# fpv.net
KiCad netlist of a schematic drawn in Altium Designer
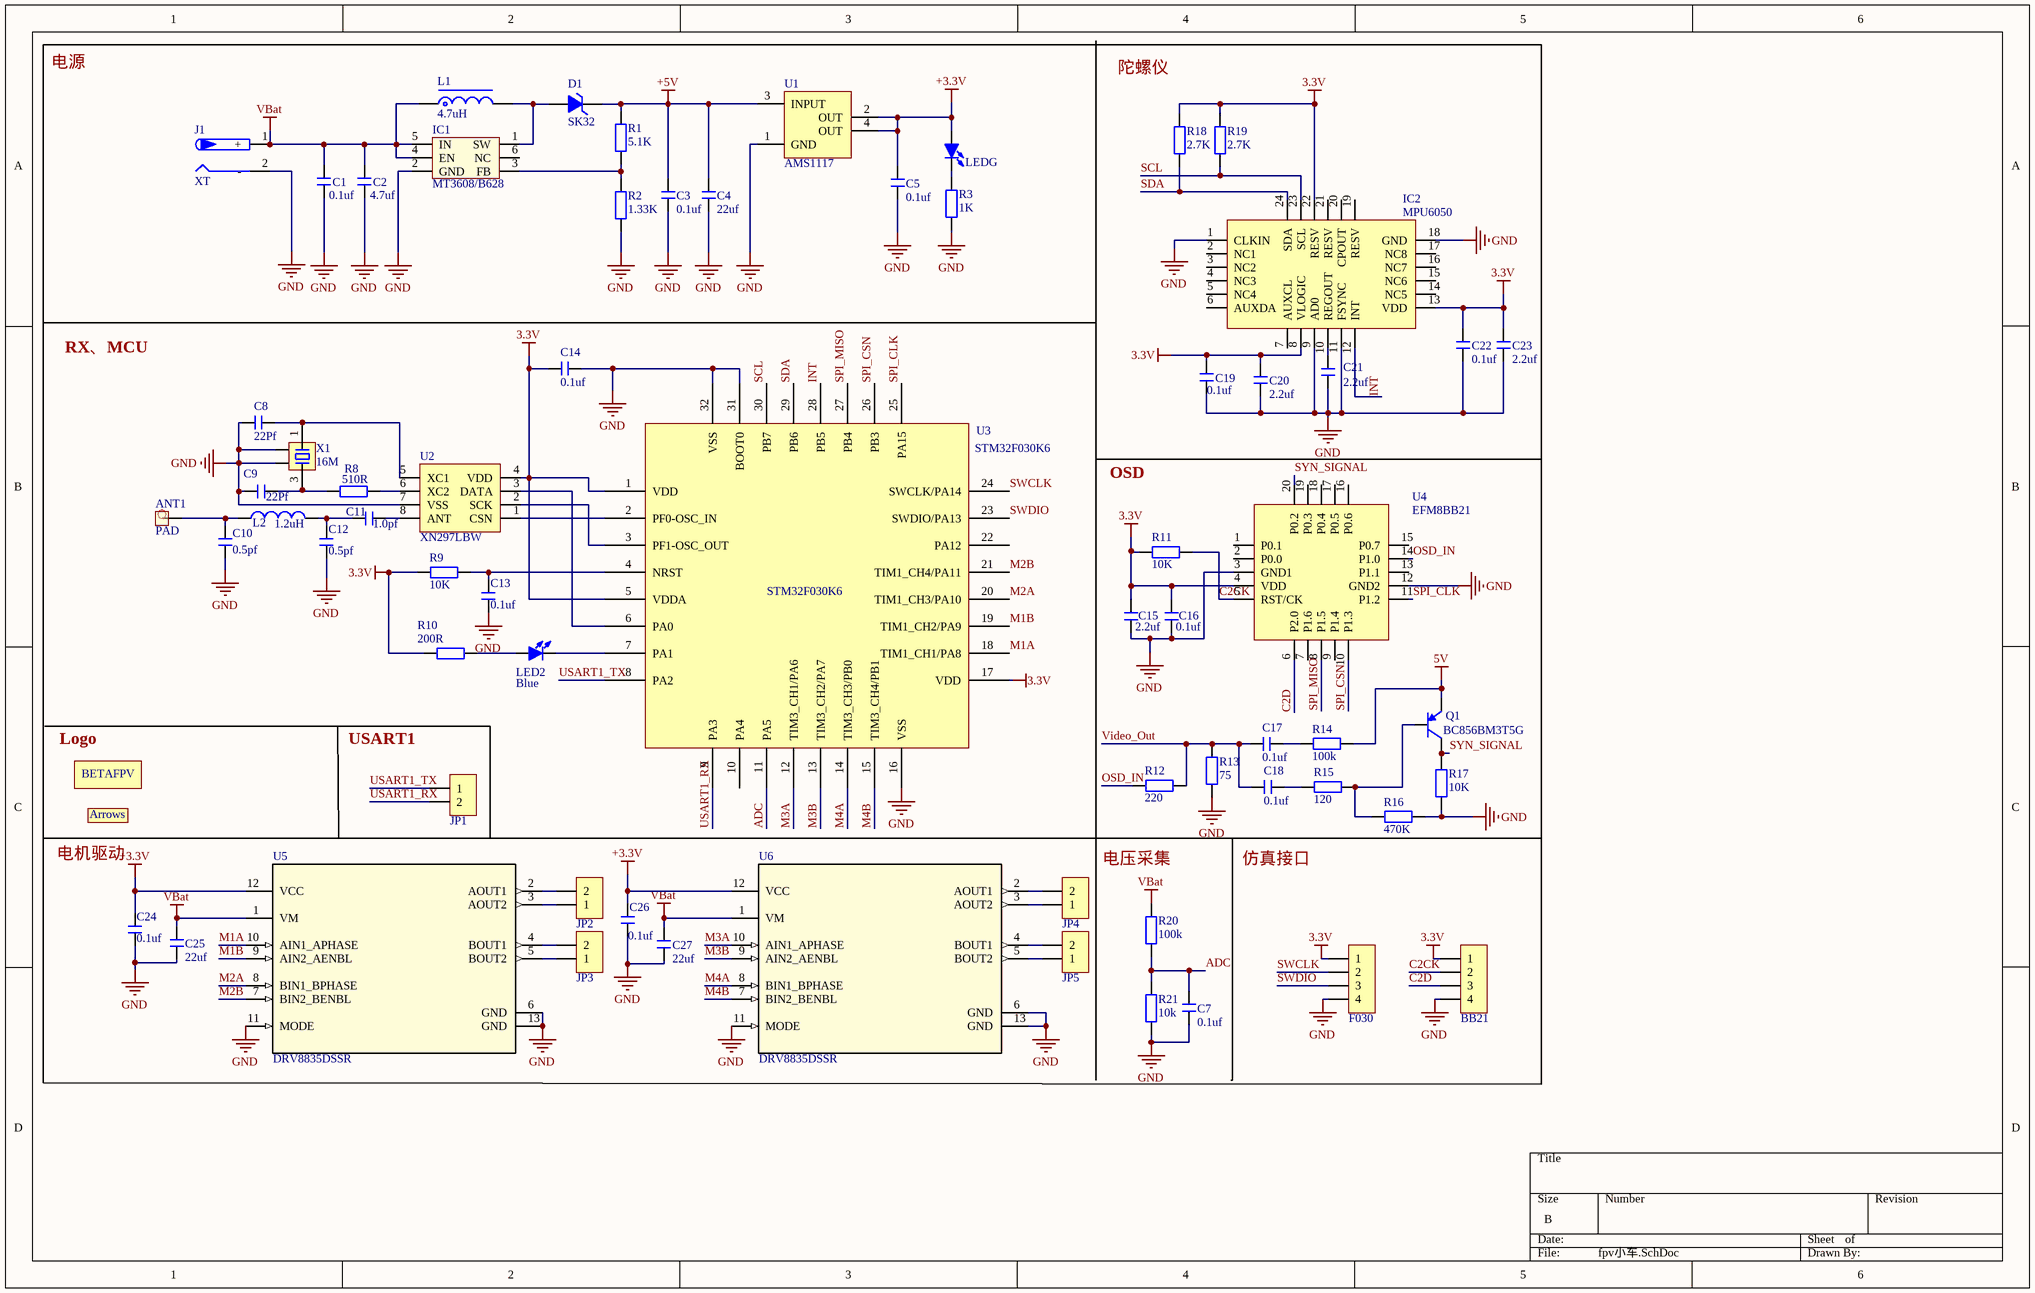
[diagram p0: fpv小车.SchDoc]

(export (version "E")
  (design (tool "Eeschema 10.0.6"))
  (components
    (comp (ref "ANT1") (value "PAD") (footprint "PAD") (libsource (lib "BetaFPV-F3-FL") (part "PAD")))
    (comp (ref "BB21")
      (value "HDR-1X4")
      (footprint "L-1.25-4P - A")
      (description "4P接插件")
      (fields (field (name "版权归属") "源创客"))
      (libsource (lib "4.6   - 接插件-脚距2.54") (part "Header 4"))
    )
    (comp (ref "C1") (value "0.1uf") (footprint "0402-C-S-1.33*0.5") (libsource (lib "L-电阻电容电感") (part "C")))
    (comp (ref "C2") (value "4.7uf") (footprint "0402-C-S-1.33*0.5") (libsource (lib "L-电阻电容电感") (part "C")))
    (comp (ref "C3") (value "0.1uf") (footprint "0402-C-S-1.33*0.5") (libsource (lib "L-电阻电容电感") (part "C")))
    (comp (ref "C4") (value "22uf") (footprint "C 0603_L") (libsource (lib "L-电阻电容电感") (part "C")))
    (comp (ref "C5") (value "0.1uf") (footprint "0402-C-S-1.33*0.5") (libsource (lib "L-电阻电容电感") (part "C")))
    (comp (ref "C7")
      (value "0.1uf")
      (footprint "L-电阻电容电感:0402-C-S-1.33*0.5")
      (libsource (lib "L-电阻电容电感") (part "C"))
    )
    (comp (ref "C8")
      (value "22Pf")
      (footprint "L-电阻电容电感:0402-C-S-1.33*0.5")
      (libsource (lib "L-电阻电容电感") (part "C"))
    )
    (comp (ref "C9")
      (value "22Pf")
      (footprint "L-电阻电容电感:0402-C-S-1.33*0.5")
      (libsource (lib "L-电阻电容电感") (part "C"))
    )
    (comp (ref "C10")
      (value "0.5pf")
      (footprint "L-电阻电容电感:0402-C-S-1.33*0.5")
      (libsource (lib "L-电阻电容电感") (part "C"))
    )
    (comp (ref "C11")
      (value "1.0pf")
      (footprint "L-电阻电容电感:0402-C-S-1.33*0.5")
      (libsource (lib "L-电阻电容电感") (part "C"))
    )
    (comp (ref "C12")
      (value "0.5pf")
      (footprint "L-电阻电容电感:0402-C-S-1.33*0.5")
      (libsource (lib "L-电阻电容电感") (part "C"))
    )
    (comp (ref "C13")
      (value "0.1uf")
      (footprint "L-电阻电容电感:0402-C-S-1.33*0.5")
      (libsource (lib "L-电阻电容电感") (part "C"))
    )
    (comp (ref "C14")
      (value "0.1uf")
      (footprint "L-电阻电容电感:0402-C-S-1.33*0.5")
      (libsource (lib "L-电阻电容电感") (part "C"))
    )
    (comp (ref "C15")
      (value "2.2uf")
      (footprint "L-电阻电容电感:0402-C-S-1.33*0.5")
      (libsource (lib "L-电阻电容电感") (part "C"))
    )
    (comp (ref "C16")
      (value "0.1uf")
      (footprint "L-电阻电容电感:0402-C-S-1.33*0.5")
      (libsource (lib "L-电阻电容电感") (part "C"))
    )
    (comp (ref "C17")
      (value "0.1uf")
      (footprint "L-电阻电容电感:0402-C-S-1.33*0.5")
      (libsource (lib "L-电阻电容电感") (part "C"))
    )
    (comp (ref "C18")
      (value "0.1uf")
      (footprint "L-电阻电容电感:0402-C-S-1.33*0.5")
      (libsource (lib "L-电阻电容电感") (part "C"))
    )
    (comp (ref "C19")
      (value "0.1uf")
      (footprint "L-电阻电容电感:0402-C-S-1.33*0.5")
      (libsource (lib "L-电阻电容电感") (part "C"))
    )
    (comp (ref "C20")
      (value "2.2uf")
      (footprint "L-电阻电容电感:0402-C-S-1.33*0.5")
      (libsource (lib "L-电阻电容电感") (part "C"))
    )
    (comp (ref "C21")
      (value "2.2uf")
      (footprint "L-电阻电容电感:0402-C-S-1.33*0.5")
      (libsource (lib "L-电阻电容电感") (part "C"))
    )
    (comp (ref "C22")
      (value "0.1uf")
      (footprint "L-电阻电容电感:0402-C-S-1.33*0.5")
      (libsource (lib "L-电阻电容电感") (part "C"))
    )
    (comp (ref "C23")
      (value "2.2uf")
      (footprint "L-电阻电容电感:0402-C-S-1.33*0.5")
      (libsource (lib "L-电阻电容电感") (part "C"))
    )
    (comp (ref "C24")
      (value "0.1uf")
      (footprint "L-电阻电容电感:0402-C-S-1.33*0.5")
      (libsource (lib "L-电阻电容电感") (part "C"))
    )
    (comp (ref "C25")
      (value "22uf")
      (footprint "0805-C-3.0*1.4")
      (description "无极性贴片电容")
      (fields (field (name "版权归属") "源创客"))
      (libsource (lib "3.1   - 电阻-电容-电感") (part "C"))
    )
    (comp (ref "C26")
      (value "0.1uf")
      (footprint "L-电阻电容电感:0402-C-S-1.33*0.5")
      (libsource (lib "L-电阻电容电感") (part "C"))
    )
    (comp (ref "C27")
      (value "22uf")
      (footprint "0805-C-3.0*1.4")
      (description "无极性贴片电容")
      (fields (field (name "版权归属") "源创客"))
      (libsource (lib "3.1   - 电阻-电容-电感") (part "C"))
    )
    (comp (ref "D1") (value "SK32") (footprint "SOD-123") (libsource (lib "L-二极管、稳压管") (part "1N4148WT")))
    (comp (ref "F030")
      (value "HDR-1X4")
      (footprint "L-1.25-4P - A")
      (description "4P接插件")
      (fields (field (name "版权归属") "源创客"))
      (libsource (lib "4.2   - 接插件-脚距1.25") (part "Header 4"))
    )
    (comp (ref "IC1")
      (value "MT3608/B628")
      (footprint "L - SOT23-6L")
      (libsource (lib "L-电源芯片") (part "MT3608/B628"))
    )
    (comp (ref "IC2")
      (value "MPU6050")
      (footprint "L-传感器件:QFN24 - 4*4*0.9")
      (fields (field (name "版权所有") "河池学院智能控制重点实验室"))
      (libsource (lib "L-传感器件") (part "MPU6050"))
    )
    (comp (ref "J1") (value "XT") (footprint "L - 20AWG") (libsource (lib "L-接口类") (part "电源接口")))
    (comp (ref "JP1")
      (value "HDR-1X2")
      (footprint "L-1.5-2p")
      (fields (field (name "版权归属") "Ly"))
      (libsource (lib "L-测试孔") (part "Header 2"))
    )
    (comp (ref "JP2")
      (value "HDR-1X2")
      (footprint "MX 1.25-LI-2P")
      (description "2P接插件")
      (fields (field (name "版权归属") "源创客"))
      (libsource (lib "") (part "Header 2_1"))
    )
    (comp (ref "JP3")
      (value "HDR-1X2")
      (footprint "MX 1.25-LI-2P")
      (description "2P接插件")
      (fields (field (name "版权归属") "源创客"))
      (libsource (lib "4.2   - 接插件-脚距1.25") (part "Header 2"))
    )
    (comp (ref "JP4")
      (value "HDR-1X2")
      (footprint "MX 1.25-LI-2P")
      (description "2P接插件")
      (fields (field (name "版权归属") "源创客"))
      (libsource (lib "4.2   - 接插件-脚距1.25") (part "Header 2"))
    )
    (comp (ref "JP5")
      (value "HDR-1X2")
      (footprint "MX 1.25-LI-2P")
      (description "2P接插件")
      (fields (field (name "版权归属") "源创客"))
      (libsource (lib "4.2   - 接插件-脚距1.25") (part "Header 2"))
    )
    (comp (ref "L1")
      (value "4.7uH")
      (footprint "NR3010")
      (description "NR磁胶电感")
      (fields (field (name "版权归属") "源创客"))
      (libsource (lib "3.1   - 电阻-电容-电感") (part "L-NR"))
    )
    (comp (ref "L2") (value "1.2uH") (footprint "0402-L-1.6*0.5") (libsource (lib "L-电阻电容电感") (part "L")))
    (comp (ref "LED2")
      (value "Blue")
      (footprint "LED 0603B")
      (description "贴片LED")
      (fields (field (name "版权归属") "源创客"))
      (libsource (lib "9.1   - LED") (part "LED-SMD"))
    )
    (comp (ref "LEDG") (value "LED") (footprint "L-LED 0603B") (libsource (lib "L-LED") (part "LED-2PIN")))
    (comp (ref "logo1")
      (value "BETAFPV")
      (footprint "BETAFPV-7*1.5mm")
      (fields (field (name "版权所有") "深圳市哈鸣科技有限公司"))
      (libsource (lib "BETAFPV") (part "BETAFPV"))
    )
    (comp (ref "logo2")
      (value "Arrows")
      (footprint "Arrows - B")
      (fields (field (name "版权所有") "深圳市哈鸣科技有限公司"))
      (libsource (lib "BETAFPV") (part "Arrows"))
    )
    (comp (ref "Q1")
      (value "BC856BM3T5G")
      (footprint "SOT - 723 *1.05mm")
      (description "低噪放大-PNP型")
      (fields (field (name "版权归属") "源创客"))
      (libsource (lib "6.2   - 三极管") (part "9015-SMD"))
    )
    (comp (ref "R1") (value "5.1K") (footprint "0402-R-1.38*0.5") (libsource (lib "L-电阻电容电感") (part "R")))
    (comp (ref "R2") (value "1.33K") (footprint "0402-R-1.38*0.5") (libsource (lib "L-电阻电容电感") (part "R")))
    (comp (ref "R3") (value "1K") (footprint "0402-R-1.38*0.5") (libsource (lib "L-电阻电容电感") (part "R")))
    (comp (ref "R8") (value "510R") (footprint "0402-R-1.38*0.5") (libsource (lib "L-电阻电容电感") (part "R")))
    (comp (ref "R9") (value "10K") (footprint "0402-R-1.38*0.5") (libsource (lib "L-电阻电容电感") (part "R")))
    (comp (ref "R10") (value "200R") (footprint "0402-R-1.38*0.5") (libsource (lib "L-电阻电容电感") (part "R")))
    (comp (ref "R11") (value "10K") (footprint "0402-R-1.38*0.5") (libsource (lib "L-电阻电容电感") (part "R")))
    (comp (ref "R12") (value "220") (footprint "0402-R-1.38*0.5") (libsource (lib "L-电阻电容电感") (part "R")))
    (comp (ref "R13") (value "75") (footprint "0402-R-1.38*0.5") (libsource (lib "L-电阻电容电感") (part "R")))
    (comp (ref "R14") (value "100k") (footprint "0402-R-1.38*0.5") (libsource (lib "L-电阻电容电感") (part "R")))
    (comp (ref "R15") (value "120") (footprint "0402-R-1.38*0.5") (libsource (lib "L-电阻电容电感") (part "R")))
    (comp (ref "R16") (value "470K") (footprint "0402-R-1.38*0.5") (libsource (lib "L-电阻电容电感") (part "R")))
    (comp (ref "R17") (value "10K") (footprint "0402-R-1.38*0.5") (libsource (lib "L-电阻电容电感") (part "R")))
    (comp (ref "R18") (value "2.7K") (footprint "0402-R-1.38*0.5") (libsource (lib "L-电阻电容电感") (part "R")))
    (comp (ref "R19") (value "2.7K") (footprint "0402-R-1.38*0.5") (libsource (lib "L-电阻电容电感") (part "R")))
    (comp (ref "R20") (value "100k") (footprint "0402-R-1.38*0.5") (libsource (lib "L-电阻电容电感") (part "R")))
    (comp (ref "R21") (value "10k") (footprint "0402-R-1.38*0.5") (libsource (lib "L-电阻电容电感") (part "R")))
    (comp (ref "U1") (value "AMS1117") (footprint "AMS1117-3D") (libsource (lib "L-电源芯片") (part "AMS1117")))
    (comp (ref "U2")
      (value "XN297LBW")
      (footprint "HCXY-SOIC-8")
      (libsource (lib "L-RFIC") (part "XN297LBW"))
    )
    (comp (ref "U3")
      (value "STM32F030K6")
      (footprint "LQFP:LQFP32 7X7_M")
      (libsource (lib "X_STM32") (part "STM32F030K6"))
    )
    (comp (ref "U4") (value "EFM8BB21") (footprint "L - QFN20") (libsource (lib "L-8位单片机") (part "EFM8BB21")))
    (comp (ref "U5")
      (value "DRV8835DSSR")
      (footprint "DSS0012A")
      (description "Imported")
      (fields (field (name "MANUFACTURER") "Texas Instruments"))
      (libsource (lib "2019-07-05_13-20-34") (part "DRV8835DSSR"))
    )
    (comp (ref "U6")
      (value "DRV8835DSSR")
      (footprint "DSS0012A")
      (description "Imported")
      (fields (field (name "MANUFACTURER") "Texas Instruments"))
      (libsource (lib "2019-07-05_13-20-34") (part "DRV8835DSSR"))
    )
    (comp (ref "X1")
      (value "16M")
      (footprint "OSC 3225-4P")
      (description "4脚无源晶振")
      (fields (field (name "版权归属") "源创客"))
      (libsource (lib "10.1 - 保险丝-晶振") (part "XTAL-4P"))
    )
  )
  (nets
    (net (code "1") (name "+3.3V") (class "Default")
      (node (ref "C24") (pin "2") (pinfunction "2_2") (pintype "passive"))
      (node (ref "C26") (pin "2") (pinfunction "2_2") (pintype "passive"))
      (node (ref "C5") (pin "2") (pinfunction "2_2") (pintype "passive"))
      (node (ref "LEDG") (pin "1") (pinfunction "A_1") (pintype "passive"))
      (node (ref "U1") (pin "2") (pinfunction "OUT_2") (pintype "passive"))
      (node (ref "U1") (pin "4") (pinfunction "OUT_4") (pintype "passive"))
      (node (ref "U5") (pin "12") (pinfunction "VCC_12") (pintype "power_in"))
      (node (ref "U6") (pin "12") (pinfunction "VCC_12") (pintype "power_in"))
    )
    (net (code "2") (name "+5V") (class "Default")
      (node (ref "C3") (pin "2") (pinfunction "2_2") (pintype "passive"))
      (node (ref "C4") (pin "2") (pinfunction "2_2") (pintype "passive"))
      (node (ref "D1") (pin "2") (pinfunction "2_2") (pintype "passive"))
      (node (ref "R1") (pin "2") (pinfunction "2_2") (pintype "passive"))
      (node (ref "U1") (pin "3") (pinfunction "INPUT_3") (pintype "passive"))
    )
    (net (code "3") (name "/ADC") (class "Default")
      (node (ref "C7") (pin "1") (pinfunction "1_1") (pintype "passive"))
      (node (ref "R20") (pin "2") (pinfunction "2_2") (pintype "passive"))
      (node (ref "R21") (pin "1") (pinfunction "1_1") (pintype "passive"))
      (node (ref "U3") (pin "11") (pinfunction "PA5_11") (pintype "passive"))
    )
    (net (code "4") (name "/C2CK") (class "Default")
      (node (ref "BB21") (pin "2") (pinfunction "2_2") (pintype "passive"))
      (node (ref "R11") (pin "2") (pinfunction "2_2") (pintype "passive"))
      (node (ref "U4") (pin "5") (pinfunction "RST/CK_5") (pintype "passive"))
    )
    (net (code "5") (name "/C2D") (class "Default")
      (node (ref "BB21") (pin "3") (pinfunction "3_3") (pintype "passive"))
      (node (ref "U4") (pin "6") (pinfunction "P2.0_6") (pintype "passive"))
    )
    (net (code "6") (name "/INT") (class "Default")
      (node (ref "IC2") (pin "12") (pinfunction "INT_12") (pintype "passive"))
      (node (ref "U3") (pin "28") (pinfunction "PB5_28") (pintype "passive"))
    )
    (net (code "7") (name "/M1A") (class "Default")
      (node (ref "U3") (pin "18") (pinfunction "TIM1_CH1/PA8_18") (pintype "passive"))
      (node (ref "U5") (pin "10") (pinfunction "AIN1_APHASE_10") (pintype "input"))
    )
    (net (code "8") (name "/M1B") (class "Default")
      (node (ref "U3") (pin "19") (pinfunction "TIM1_CH2/PA9_19") (pintype "passive"))
      (node (ref "U5") (pin "9") (pinfunction "AIN2_AENBL_9") (pintype "input"))
    )
    (net (code "9") (name "/M2A") (class "Default")
      (node (ref "U3") (pin "20") (pinfunction "TIM1_CH3/PA10_20") (pintype "passive"))
      (node (ref "U5") (pin "8") (pinfunction "BIN1_BPHASE_8") (pintype "input"))
    )
    (net (code "10") (name "/M2B") (class "Default")
      (node (ref "U3") (pin "21") (pinfunction "TIM1_CH4/PA11_21") (pintype "passive"))
      (node (ref "U5") (pin "7") (pinfunction "BIN2_BENBL_7") (pintype "input"))
    )
    (net (code "11") (name "/M3A") (class "Default")
      (node (ref "U3") (pin "12") (pinfunction "TIM3_CH1/PA6_12") (pintype "passive"))
      (node (ref "U6") (pin "10") (pinfunction "AIN1_APHASE_10") (pintype "input"))
    )
    (net (code "12") (name "/M3B") (class "Default")
      (node (ref "U3") (pin "13") (pinfunction "TIM3_CH2/PA7_13") (pintype "passive"))
      (node (ref "U6") (pin "9") (pinfunction "AIN2_AENBL_9") (pintype "input"))
    )
    (net (code "13") (name "/M4A") (class "Default")
      (node (ref "U3") (pin "14") (pinfunction "TIM3_CH3/PB0_14") (pintype "passive"))
      (node (ref "U6") (pin "8") (pinfunction "BIN1_BPHASE_8") (pintype "input"))
    )
    (net (code "14") (name "/M4B") (class "Default")
      (node (ref "U3") (pin "15") (pinfunction "TIM3_CH4/PB1_15") (pintype "passive"))
      (node (ref "U6") (pin "7") (pinfunction "BIN2_BENBL_7") (pintype "input"))
    )
    (net (code "15") (name "/OSD_IN") (class "Default")
      (node (ref "R12") (pin "2") (pinfunction "2_2") (pintype "passive"))
      (node (ref "U4") (pin "14") (pinfunction "P1.0_14") (pintype "passive"))
    )
    (net (code "16") (name "/SCL") (class "Default")
      (node (ref "IC2") (pin "23") (pinfunction "SCL_23") (pintype "passive"))
      (node (ref "R19") (pin "1") (pinfunction "1_1") (pintype "passive"))
      (node (ref "U3") (pin "30") (pinfunction "PB7_30") (pintype "passive"))
    )
    (net (code "17") (name "/SDA") (class "Default")
      (node (ref "IC2") (pin "24") (pinfunction "SDA_24") (pintype "passive"))
      (node (ref "R18") (pin "1") (pinfunction "1_1") (pintype "passive"))
      (node (ref "U3") (pin "29") (pinfunction "PB6_29") (pintype "passive"))
    )
    (net (code "18") (name "/SPI_CLK") (class "Default")
      (node (ref "U3") (pin "25") (pinfunction "PA15_25") (pintype "passive"))
      (node (ref "U4") (pin "11") (pinfunction "P1.2_11") (pintype "passive"))
    )
    (net (code "19") (name "/SPI_CSN") (class "Default")
      (node (ref "U3") (pin "26") (pinfunction "PB3_26") (pintype "passive"))
      (node (ref "U4") (pin "10") (pinfunction "P1.3_10") (pintype "passive"))
    )
    (net (code "20") (name "/SPI_MISO") (class "Default")
      (node (ref "U3") (pin "27") (pinfunction "PB4_27") (pintype "passive"))
      (node (ref "U4") (pin "8") (pinfunction "P1.5_8") (pintype "passive"))
    )
    (net (code "21") (name "/SWCLK") (class "Default")
      (node (ref "F030") (pin "2") (pinfunction "2_2") (pintype "passive"))
      (node (ref "U3") (pin "24") (pinfunction "SWCLK/PA14_24") (pintype "passive"))
    )
    (net (code "22") (name "/SWDIO") (class "Default")
      (node (ref "F030") (pin "3") (pinfunction "3_3") (pintype "passive"))
      (node (ref "U3") (pin "23") (pinfunction "SWDIO/PA13_23") (pintype "passive"))
    )
    (net (code "23") (name "/SYN_SIGNAL") (class "Default")
      (node (ref "Q1") (pin "3") (pinfunction "C_3") (pintype "passive"))
      (node (ref "R17") (pin "2") (pinfunction "2_2") (pintype "passive"))
      (node (ref "U4") (pin "20") (pinfunction "P0.2_20") (pintype "passive"))
    )
    (net (code "24") (name "/USART1_RX") (class "Default")
      (node (ref "JP1") (pin "2") (pinfunction "2_2") (pintype "passive"))
      (node (ref "U3") (pin "9") (pinfunction "PA3_9") (pintype "passive"))
    )
    (net (code "25") (name "/USART1_TX") (class "Default")
      (node (ref "JP1") (pin "1") (pinfunction "1_1") (pintype "passive"))
      (node (ref "U3") (pin "8") (pinfunction "PA2_8") (pintype "passive"))
    )
    (net (code "26") (name "/Video_Out") (class "Default")
      (node (ref "C17") (pin "2") (pinfunction "2_2") (pintype "passive"))
      (node (ref "C18") (pin "2") (pinfunction "2_2") (pintype "passive"))
      (node (ref "R12") (pin "1") (pinfunction "1_1") (pintype "passive"))
      (node (ref "R13") (pin "2") (pinfunction "2_2") (pintype "passive"))
    )
    (net (code "27") (name "3.3V") (class "Default")
      (node (ref "BB21") (pin "1") (pinfunction "1_1") (pintype "passive"))
      (node (ref "C14") (pin "1") (pinfunction "1_1") (pintype "passive"))
      (node (ref "C15") (pin "2") (pinfunction "2_2") (pintype "passive"))
      (node (ref "C16") (pin "2") (pinfunction "2_2") (pintype "passive"))
      (node (ref "C19") (pin "2") (pinfunction "2_2") (pintype "passive"))
      (node (ref "C20") (pin "2") (pinfunction "2_2") (pintype "passive"))
      (node (ref "C22") (pin "2") (pinfunction "2_2") (pintype "passive"))
      (node (ref "C23") (pin "2") (pinfunction "2_2") (pintype "passive"))
      (node (ref "F030") (pin "1") (pinfunction "1_1") (pintype "passive"))
      (node (ref "IC2") (pin "13") (pinfunction "VDD_13") (pintype "passive"))
      (node (ref "IC2") (pin "22") (pinfunction "RESV_22") (pintype "passive"))
      (node (ref "IC2") (pin "8") (pinfunction "VLOGIC_8") (pintype "passive"))
      (node (ref "R10") (pin "2") (pinfunction "2_2") (pintype "passive"))
      (node (ref "R11") (pin "1") (pinfunction "1_1") (pintype "passive"))
      (node (ref "R18") (pin "2") (pinfunction "2_2") (pintype "passive"))
      (node (ref "R19") (pin "2") (pinfunction "2_2") (pintype "passive"))
      (node (ref "R9") (pin "2") (pinfunction "2_2") (pintype "passive"))
      (node (ref "U2") (pin "4") (pinfunction "VDD_4") (pintype "passive"))
      (node (ref "U3") (pin "1") (pinfunction "VDD_1") (pintype "passive"))
      (node (ref "U3") (pin "17") (pinfunction "VDD_17") (pintype "passive"))
      (node (ref "U3") (pin "5") (pinfunction "VDDA_5") (pintype "passive"))
      (node (ref "U4") (pin "4") (pinfunction "VDD_4") (pintype "passive"))
    )
    (net (code "28") (name "5V") (class "Default")
      (node (ref "Q1") (pin "2") (pinfunction "E_2") (pintype "passive"))
      (node (ref "R14") (pin "1") (pinfunction "1_1") (pintype "passive"))
    )
    (net (code "29") (name "GND") (class "Default")
      (node (ref "BB21") (pin "4") (pinfunction "4_4") (pintype "passive"))
      (node (ref "C1") (pin "1") (pinfunction "1_1") (pintype "passive"))
      (node (ref "C10") (pin "1") (pinfunction "1_1") (pintype "passive"))
      (node (ref "C12") (pin "1") (pinfunction "1_1") (pintype "passive"))
      (node (ref "C13") (pin "1") (pinfunction "1_1") (pintype "passive"))
      (node (ref "C14") (pin "2") (pinfunction "2_2") (pintype "passive"))
      (node (ref "C15") (pin "1") (pinfunction "1_1") (pintype "passive"))
      (node (ref "C16") (pin "1") (pinfunction "1_1") (pintype "passive"))
      (node (ref "C19") (pin "1") (pinfunction "1_1") (pintype "passive"))
      (node (ref "C2") (pin "1") (pinfunction "1_1") (pintype "passive"))
      (node (ref "C20") (pin "1") (pinfunction "1_1") (pintype "passive"))
      (node (ref "C21") (pin "1") (pinfunction "1_1") (pintype "passive"))
      (node (ref "C22") (pin "1") (pinfunction "1_1") (pintype "passive"))
      (node (ref "C23") (pin "1") (pinfunction "1_1") (pintype "passive"))
      (node (ref "C24") (pin "1") (pinfunction "1_1") (pintype "passive"))
      (node (ref "C25") (pin "1") (pinfunction "1_1") (pintype "passive"))
      (node (ref "C26") (pin "1") (pinfunction "1_1") (pintype "passive"))
      (node (ref "C27") (pin "1") (pinfunction "1_1") (pintype "passive"))
      (node (ref "C3") (pin "1") (pinfunction "1_1") (pintype "passive"))
      (node (ref "C4") (pin "1") (pinfunction "1_1") (pintype "passive"))
      (node (ref "C5") (pin "1") (pinfunction "1_1") (pintype "passive"))
      (node (ref "C7") (pin "2") (pinfunction "2_2") (pintype "passive"))
      (node (ref "C8") (pin "2") (pinfunction "2_2") (pintype "passive"))
      (node (ref "C9") (pin "1") (pinfunction "1_1") (pintype "passive"))
      (node (ref "F030") (pin "4") (pinfunction "4_4") (pintype "passive"))
      (node (ref "IC1") (pin "2") (pinfunction "GND_2") (pintype "passive"))
      (node (ref "IC2") (pin "1") (pinfunction "CLKIN_1") (pintype "passive"))
      (node (ref "IC2") (pin "11") (pinfunction "FSYNC_11") (pintype "passive"))
      (node (ref "IC2") (pin "18") (pinfunction "GND_18") (pintype "passive"))
      (node (ref "IC2") (pin "9") (pinfunction "AD0_9") (pintype "passive"))
      (node (ref "J1") (pin "2") (pinfunction "-_2") (pintype "power_in"))
      (node (ref "R13") (pin "1") (pinfunction "1_1") (pintype "passive"))
      (node (ref "R16") (pin "2") (pinfunction "2_2") (pintype "passive"))
      (node (ref "R17") (pin "1") (pinfunction "1_1") (pintype "passive"))
      (node (ref "R2") (pin "1") (pinfunction "1_1") (pintype "passive"))
      (node (ref "R21") (pin "2") (pinfunction "2_2") (pintype "passive"))
      (node (ref "R3") (pin "1") (pinfunction "1_1") (pintype "passive"))
      (node (ref "U1") (pin "1") (pinfunction "GND_1") (pintype "passive"))
      (node (ref "U2") (pin "7") (pinfunction "VSS_7") (pintype "passive"))
      (node (ref "U3") (pin "16") (pinfunction "VSS_16") (pintype "passive"))
      (node (ref "U3") (pin "31") (pinfunction "BOOT0_31") (pintype "passive"))
      (node (ref "U3") (pin "32") (pinfunction "VSS_32") (pintype "passive"))
      (node (ref "U4") (pin "12") (pinfunction "GND2_12") (pintype "passive"))
      (node (ref "U4") (pin "3") (pinfunction "GND1_3") (pintype "passive"))
      (node (ref "U5") (pin "11") (pinfunction "MODE_11") (pintype "input"))
      (node (ref "U5") (pin "13") (pinfunction "GND_13") (pintype "power_in"))
      (node (ref "U5") (pin "6") (pinfunction "GND_6") (pintype "power_in"))
      (node (ref "U6") (pin "11") (pinfunction "MODE_11") (pintype "input"))
      (node (ref "U6") (pin "13") (pinfunction "GND_13") (pintype "power_in"))
      (node (ref "U6") (pin "6") (pinfunction "GND_6") (pintype "power_in"))
      (node (ref "X1") (pin "2") (pinfunction "2_2") (pintype "passive"))
      (node (ref "X1") (pin "4") (pinfunction "4_4") (pintype "passive"))
    )
    (net (code "30") (name "Net-(ANT1-24)") (class "Default")
      (node (ref "ANT1") (pin "0") (pinfunction "24_0") (pintype "passive"))
      (node (ref "C10") (pin "2") (pinfunction "2_2") (pintype "passive"))
      (node (ref "L2") (pin "1") (pinfunction "1_1") (pintype "passive"))
    )
    (net (code "31") (name "Net-(C9-Pad2)") (class "Default")
      (node (ref "C9") (pin "2") (pinfunction "2_2") (pintype "passive"))
      (node (ref "R8") (pin "1") (pinfunction "1_1") (pintype "passive"))
      (node (ref "X1") (pin "3") (pinfunction "3_3") (pintype "passive"))
    )
    (net (code "32") (name "Net-(C11-Pad2)") (class "Default")
      (node (ref "C11") (pin "2") (pinfunction "2_2") (pintype "passive"))
      (node (ref "C12") (pin "2") (pinfunction "2_2") (pintype "passive"))
      (node (ref "L2") (pin "2") (pinfunction "2_2") (pintype "passive"))
    )
    (net (code "33") (name "Net-(C17-Pad1)") (class "Default")
      (node (ref "C17") (pin "1") (pinfunction "1_1") (pintype "passive"))
      (node (ref "R14") (pin "2") (pinfunction "2_2") (pintype "passive"))
    )
    (net (code "34") (name "Net-(C18-Pad1)") (class "Default")
      (node (ref "C18") (pin "1") (pinfunction "1_1") (pintype "passive"))
      (node (ref "R15") (pin "2") (pinfunction "2_2") (pintype "passive"))
    )
    (net (code "35") (name "Net-(IC1-FB)") (class "Default")
      (node (ref "IC1") (pin "3") (pinfunction "FB_3") (pintype "passive"))
      (node (ref "R1") (pin "1") (pinfunction "1_1") (pintype "passive"))
      (node (ref "R2") (pin "2") (pinfunction "2_2") (pintype "passive"))
    )
    (net (code "36") (name "Net-(IC1-SW)") (class "Default")
      (node (ref "D1") (pin "1") (pinfunction "1_1") (pintype "passive"))
      (node (ref "IC1") (pin "1") (pinfunction "SW_1") (pintype "passive"))
      (node (ref "L1") (pin "2") (pinfunction "2_2") (pintype "passive"))
    )
    (net (code "37") (name "Net-(IC2-REGOUT)") (class "Default")
      (node (ref "C21") (pin "2") (pinfunction "2_2") (pintype "passive"))
      (node (ref "IC2") (pin "10") (pinfunction "REGOUT_10") (pintype "passive"))
    )
    (net (code "38") (name "Net-(LED2-A)") (class "Default")
      (node (ref "LED2") (pin "1") (pinfunction "A_1") (pintype "passive"))
      (node (ref "R10") (pin "1") (pinfunction "1_1") (pintype "passive"))
    )
    (net (code "39") (name "Net-(LED2-K)") (class "Default")
      (node (ref "LED2") (pin "2") (pinfunction "K_2") (pintype "passive"))
      (node (ref "U3") (pin "7") (pinfunction "PA1_7") (pintype "passive"))
    )
    (net (code "40") (name "Net-(LEDG-K)") (class "Default")
      (node (ref "LEDG") (pin "2") (pinfunction "K_2") (pintype "passive"))
      (node (ref "R3") (pin "2") (pinfunction "2_2") (pintype "passive"))
    )
    (net (code "41") (name "Net-(Q1-B)") (class "Default")
      (node (ref "Q1") (pin "1") (pinfunction "B_1") (pintype "passive"))
      (node (ref "R15") (pin "1") (pinfunction "1_1") (pintype "passive"))
      (node (ref "R16") (pin "1") (pinfunction "1_1") (pintype "passive"))
    )
    (net (code "42") (name "Net-(U2-ANT)") (class "Default")
      (node (ref "C11") (pin "1") (pinfunction "1_1") (pintype "passive"))
      (node (ref "U2") (pin "8") (pinfunction "ANT_8") (pintype "passive"))
    )
    (net (code "43") (name "Net-(U2-CSN)") (class "Default")
      (node (ref "U2") (pin "1") (pinfunction "CSN_1") (pintype "passive"))
      (node (ref "U3") (pin "2") (pinfunction "PF0-OSC_IN_2") (pintype "passive"))
    )
    (net (code "44") (name "Net-(U2-DATA)") (class "Default")
      (node (ref "U2") (pin "3") (pinfunction "DATA_3") (pintype "passive"))
      (node (ref "U3") (pin "6") (pinfunction "PA0_6") (pintype "passive"))
    )
    (net (code "45") (name "Net-(U2-SCK)") (class "Default")
      (node (ref "U2") (pin "2") (pinfunction "SCK_2") (pintype "passive"))
      (node (ref "U3") (pin "3") (pinfunction "PF1-OSC_OUT_3") (pintype "passive"))
    )
    (net (code "46") (name "Net-(U2-XC1)") (class "Default")
      (node (ref "C8") (pin "1") (pinfunction "1_1") (pintype "passive"))
      (node (ref "U2") (pin "5") (pinfunction "XC1_5") (pintype "passive"))
      (node (ref "X1") (pin "1") (pinfunction "1_1") (pintype "passive"))
    )
    (net (code "47") (name "Net-(U2-XC2)") (class "Default")
      (node (ref "R8") (pin "2") (pinfunction "2_2") (pintype "passive"))
      (node (ref "U2") (pin "6") (pinfunction "XC2_6") (pintype "passive"))
    )
    (net (code "48") (name "Net-(U3-NRST)") (class "Default")
      (node (ref "C13") (pin "2") (pinfunction "2_2") (pintype "passive"))
      (node (ref "R9") (pin "1") (pinfunction "1_1") (pintype "passive"))
      (node (ref "U3") (pin "4") (pinfunction "NRST_4") (pintype "passive"))
    )
    (net (code "49") (name "Net-(U5-AOUT1)") (class "Default")
      (node (ref "JP2") (pin "2") (pinfunction "2_2") (pintype "passive"))
      (node (ref "U5") (pin "2") (pinfunction "AOUT1_2") (pintype "output"))
    )
    (net (code "50") (name "Net-(U5-AOUT2)") (class "Default")
      (node (ref "JP2") (pin "1") (pinfunction "1_1") (pintype "passive"))
      (node (ref "U5") (pin "3") (pinfunction "AOUT2_3") (pintype "output"))
    )
    (net (code "51") (name "Net-(U5-BOUT1)") (class "Default")
      (node (ref "JP3") (pin "2") (pinfunction "2_2") (pintype "passive"))
      (node (ref "U5") (pin "4") (pinfunction "BOUT1_4") (pintype "output"))
    )
    (net (code "52") (name "Net-(U5-BOUT2)") (class "Default")
      (node (ref "JP3") (pin "1") (pinfunction "1_1") (pintype "passive"))
      (node (ref "U5") (pin "5") (pinfunction "BOUT2_5") (pintype "output"))
    )
    (net (code "53") (name "Net-(U6-AOUT1)") (class "Default")
      (node (ref "JP4") (pin "2") (pinfunction "2_2") (pintype "passive"))
      (node (ref "U6") (pin "2") (pinfunction "AOUT1_2") (pintype "output"))
    )
    (net (code "54") (name "Net-(U6-AOUT2)") (class "Default")
      (node (ref "JP4") (pin "1") (pinfunction "1_1") (pintype "passive"))
      (node (ref "U6") (pin "3") (pinfunction "AOUT2_3") (pintype "output"))
    )
    (net (code "55") (name "Net-(U6-BOUT1)") (class "Default")
      (node (ref "JP5") (pin "2") (pinfunction "2_2") (pintype "passive"))
      (node (ref "U6") (pin "4") (pinfunction "BOUT1_4") (pintype "output"))
    )
    (net (code "56") (name "Net-(U6-BOUT2)") (class "Default")
      (node (ref "JP5") (pin "1") (pinfunction "1_1") (pintype "passive"))
      (node (ref "U6") (pin "5") (pinfunction "BOUT2_5") (pintype "output"))
    )
    (net (code "57") (name "VBat") (class "Default")
      (node (ref "C1") (pin "2") (pinfunction "2_2") (pintype "passive"))
      (node (ref "C2") (pin "2") (pinfunction "2_2") (pintype "passive"))
      (node (ref "C25") (pin "2") (pinfunction "2_2") (pintype "passive"))
      (node (ref "C27") (pin "2") (pinfunction "2_2") (pintype "passive"))
      (node (ref "IC1") (pin "4") (pinfunction "EN_4") (pintype "passive"))
      (node (ref "IC1") (pin "5") (pinfunction "IN_5") (pintype "passive"))
      (node (ref "J1") (pin "1") (pinfunction "+_1") (pintype "power_in"))
      (node (ref "L1") (pin "1") (pinfunction "1_1") (pintype "passive"))
      (node (ref "R20") (pin "1") (pinfunction "1_1") (pintype "passive"))
      (node (ref "U5") (pin "1") (pinfunction "VM_1") (pintype "power_in"))
      (node (ref "U6") (pin "1") (pinfunction "VM_1") (pintype "power_in"))
    )
    (net (code "58") (name "unconnected-(IC1-NC-Pad6)") (class "Default")
      (node (ref "IC1") (pin "6") (pinfunction "NC_6") (pintype "passive"))
    )
    (net (code "59") (name "unconnected-(IC2-AUXCL-Pad7)") (class "Default")
      (node (ref "IC2") (pin "7") (pinfunction "AUXCL_7") (pintype "passive"))
    )
    (net (code "60") (name "unconnected-(IC2-AUXDA-Pad6)") (class "Default")
      (node (ref "IC2") (pin "6") (pinfunction "AUXDA_6") (pintype "passive"))
    )
    (net (code "61") (name "unconnected-(IC2-CPOUT-Pad20)") (class "Default")
      (node (ref "IC2") (pin "20") (pinfunction "CPOUT_20") (pintype "passive"))
    )
    (net (code "62") (name "unconnected-(IC2-NC1-Pad2)") (class "Default")
      (node (ref "IC2") (pin "2") (pinfunction "NC1_2") (pintype "passive"))
    )
    (net (code "63") (name "unconnected-(IC2-NC2-Pad3)") (class "Default")
      (node (ref "IC2") (pin "3") (pinfunction "NC2_3") (pintype "passive"))
    )
    (net (code "64") (name "unconnected-(IC2-NC3-Pad4)") (class "Default")
      (node (ref "IC2") (pin "4") (pinfunction "NC3_4") (pintype "passive"))
    )
    (net (code "65") (name "unconnected-(IC2-NC4-Pad5)") (class "Default")
      (node (ref "IC2") (pin "5") (pinfunction "NC4_5") (pintype "passive"))
    )
    (net (code "66") (name "unconnected-(IC2-NC5-Pad14)") (class "Default")
      (node (ref "IC2") (pin "14") (pinfunction "NC5_14") (pintype "passive"))
    )
    (net (code "67") (name "unconnected-(IC2-NC6-Pad15)") (class "Default")
      (node (ref "IC2") (pin "15") (pinfunction "NC6_15") (pintype "passive"))
    )
    (net (code "68") (name "unconnected-(IC2-NC7-Pad16)") (class "Default")
      (node (ref "IC2") (pin "16") (pinfunction "NC7_16") (pintype "passive"))
    )
    (net (code "69") (name "unconnected-(IC2-NC8-Pad17)") (class "Default")
      (node (ref "IC2") (pin "17") (pinfunction "NC8_17") (pintype "passive"))
    )
    (net (code "70") (name "unconnected-(IC2-RESV-Pad19)") (class "Default")
      (node (ref "IC2") (pin "19") (pinfunction "RESV_19") (pintype "passive"))
    )
    (net (code "71") (name "unconnected-(IC2-RESV-Pad21)") (class "Default")
      (node (ref "IC2") (pin "21") (pinfunction "RESV_21") (pintype "passive"))
    )
    (net (code "72") (name "unconnected-(U3-PA4-Pad10)") (class "Default")
      (node (ref "U3") (pin "10") (pinfunction "PA4_10") (pintype "passive"))
    )
    (net (code "73") (name "unconnected-(U3-PA12-Pad22)") (class "Default")
      (node (ref "U3") (pin "22") (pinfunction "PA12_22") (pintype "passive"))
    )
    (net (code "74") (name "unconnected-(U4-P0.0-Pad2)") (class "Default")
      (node (ref "U4") (pin "2") (pinfunction "P0.0_2") (pintype "passive"))
    )
    (net (code "75") (name "unconnected-(U4-P0.1-Pad1)") (class "Default")
      (node (ref "U4") (pin "1") (pinfunction "P0.1_1") (pintype "passive"))
    )
    (net (code "76") (name "unconnected-(U4-P0.3-Pad19)") (class "Default")
      (node (ref "U4") (pin "19") (pinfunction "P0.3_19") (pintype "passive"))
    )
    (net (code "77") (name "unconnected-(U4-P0.4-Pad18)") (class "Default")
      (node (ref "U4") (pin "18") (pinfunction "P0.4_18") (pintype "passive"))
    )
    (net (code "78") (name "unconnected-(U4-P0.5-Pad17)") (class "Default")
      (node (ref "U4") (pin "17") (pinfunction "P0.5_17") (pintype "passive"))
    )
    (net (code "79") (name "unconnected-(U4-P0.6-Pad16)") (class "Default")
      (node (ref "U4") (pin "16") (pinfunction "P0.6_16") (pintype "passive"))
    )
    (net (code "80") (name "unconnected-(U4-P0.7-Pad15)") (class "Default")
      (node (ref "U4") (pin "15") (pinfunction "P0.7_15") (pintype "passive"))
    )
    (net (code "81") (name "unconnected-(U4-P1.1-Pad13)") (class "Default")
      (node (ref "U4") (pin "13") (pinfunction "P1.1_13") (pintype "passive"))
    )
    (net (code "82") (name "unconnected-(U4-P1.4-Pad9)") (class "Default")
      (node (ref "U4") (pin "9") (pinfunction "P1.4_9") (pintype "passive"))
    )
    (net (code "83") (name "unconnected-(U4-P1.6-Pad7)") (class "Default")
      (node (ref "U4") (pin "7") (pinfunction "P1.6_7") (pintype "passive"))
    )
  )
)
